# isg_adc_dac_test_board_top.net
KiCad netlist of a schematic drawn in Altium Designer
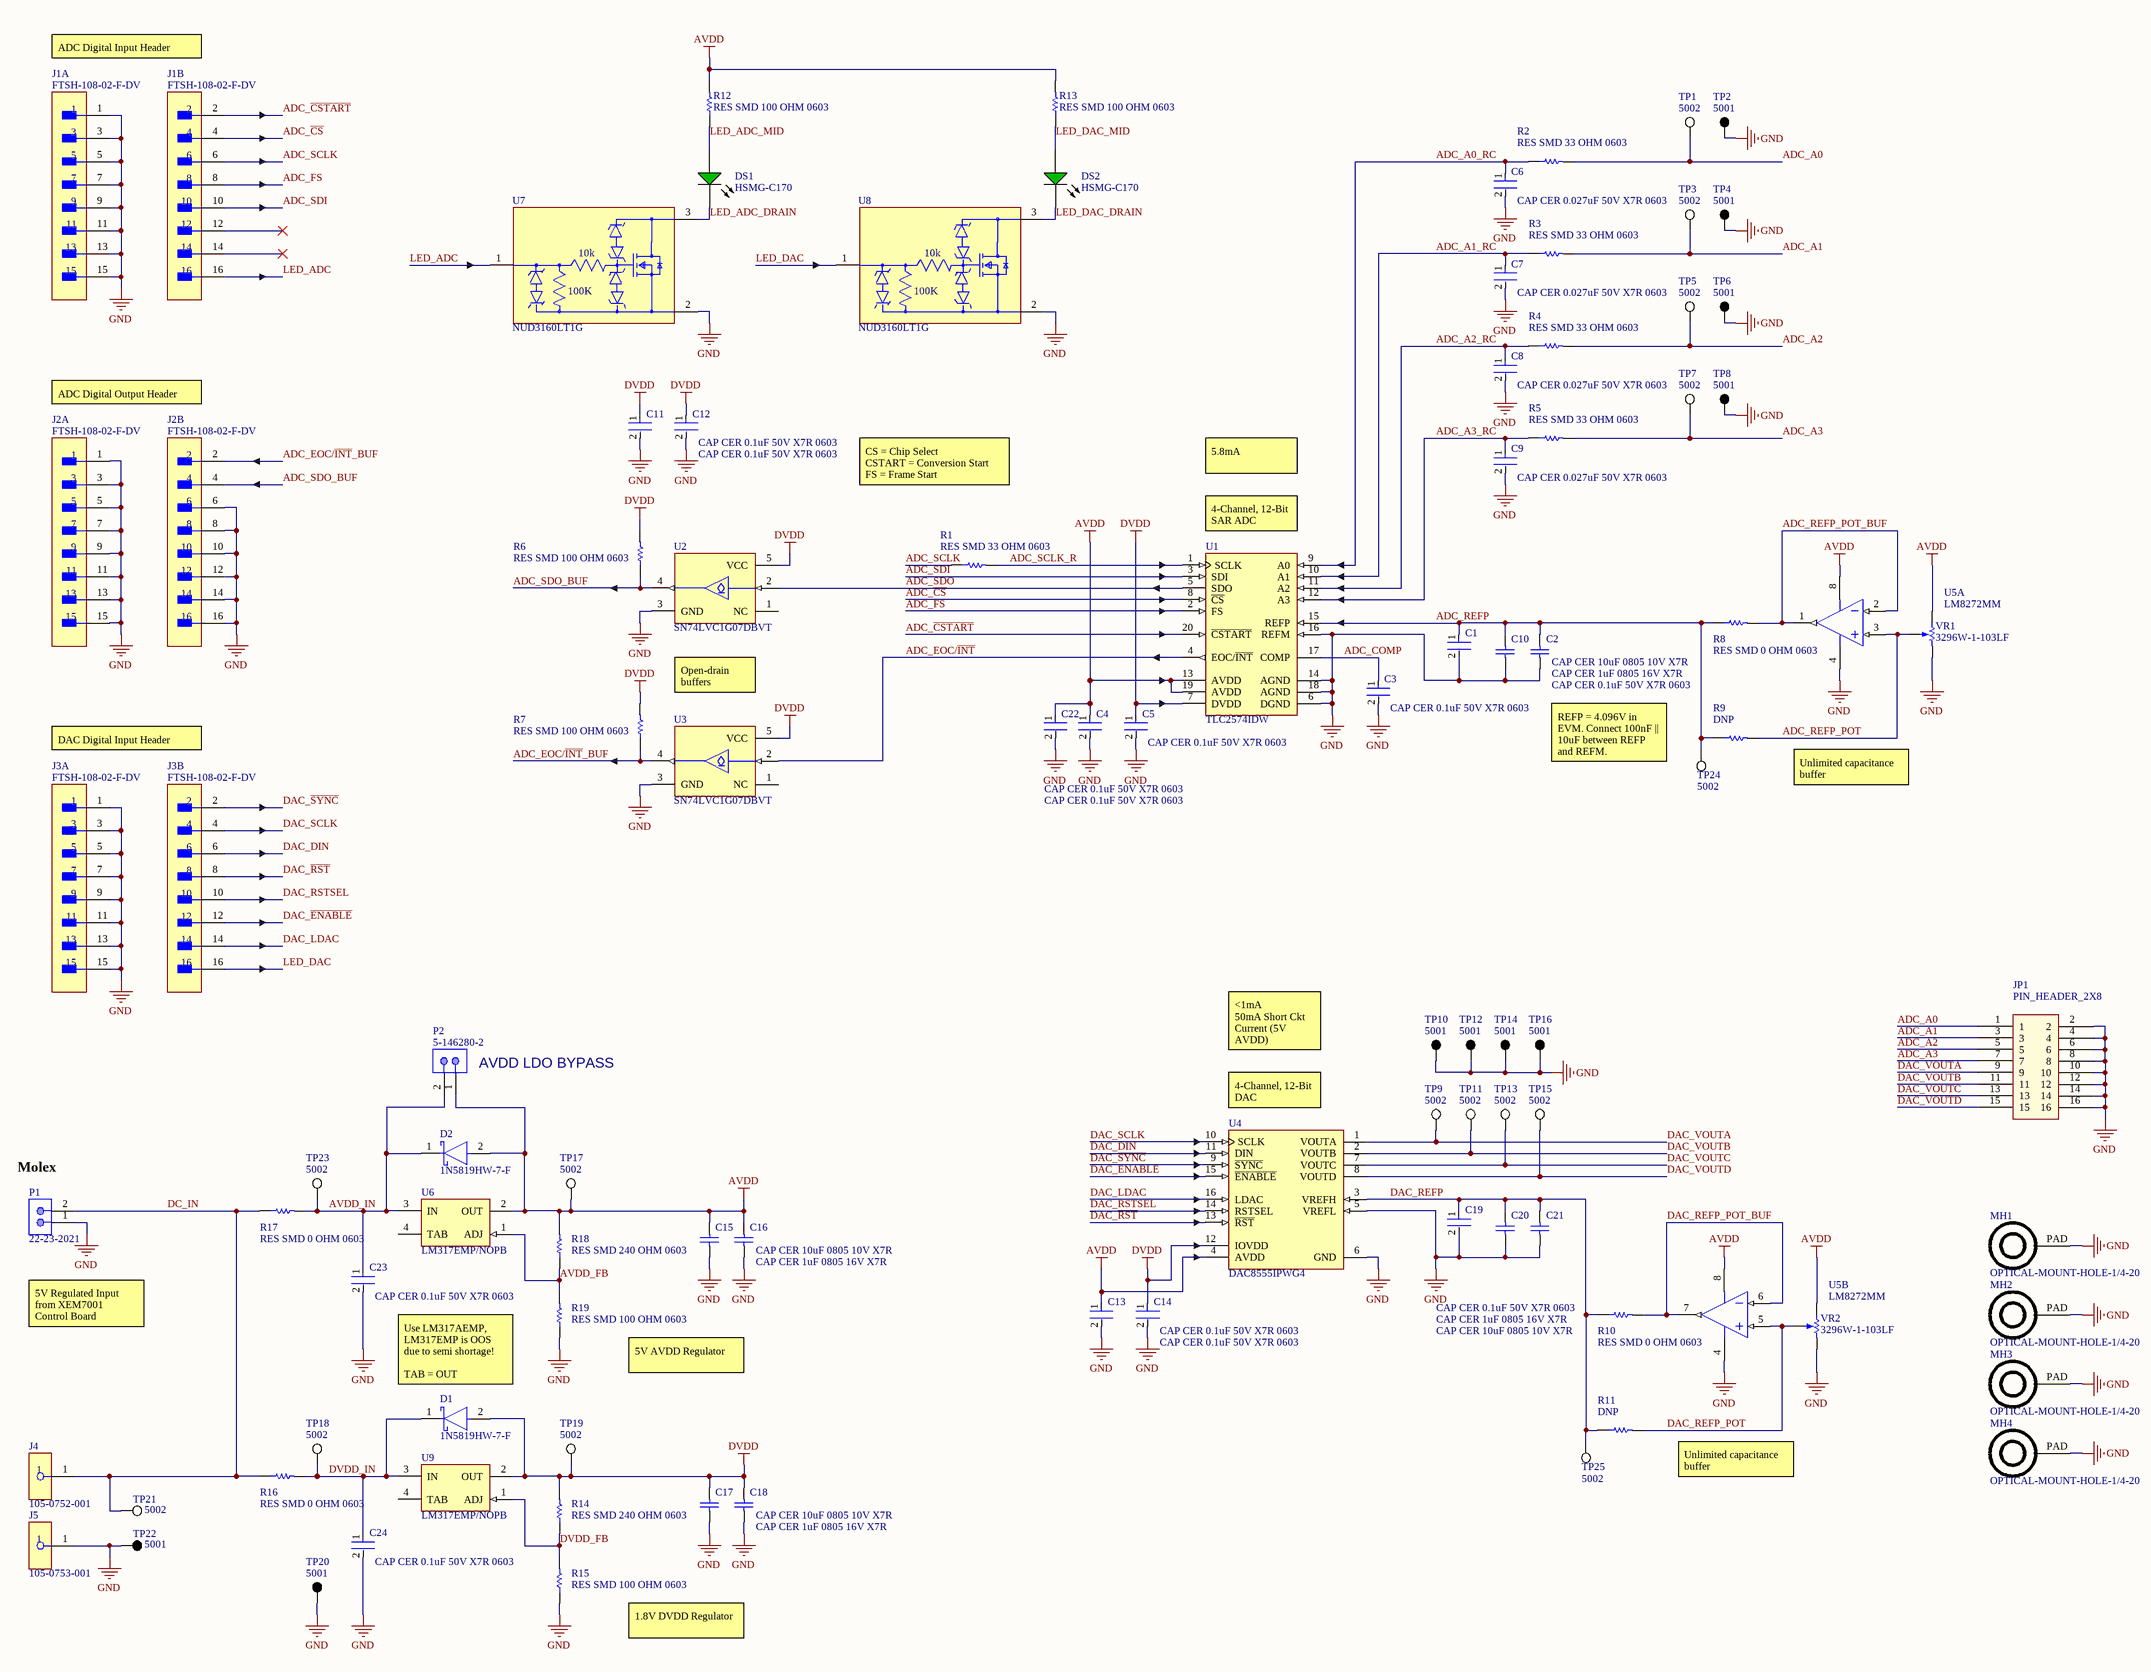
[diagram p0: isg_adc_dac_test_board_top.SchDoc]

(export (version "E")
  (design (tool "Eeschema 10.0.6"))
  (components
    (comp (ref "C1")
      (value "CAP CER 0.1uF 50V X7R 0603")
      (footprint "FP-CC0603-DA-MFG")
      (fields
        (field (name "OCTOPART") "https://octopart.com/cc0603krx7r7bb104-yageo-192941")
        (field (name "TOLERANCE") "0.1")
        (field (name "VOLTAGE") "16 V")
      )
      (libsource (lib "Altium Content Vault") (part "11868f565c42a9108669ba33697ecf6"))
    )
    (comp (ref "C2")
      (value "CAP CER 10uF 0805 10V X7R")
      (footprint "CAPC2013X140X50NL20T25")
      (fields
        (field (name "PART NUMBER") "0805ZC475KAT2A")
        (field (name "MANUFACTURER") "AVX Interconnect / Elco")
      )
      (libsource (lib "Altium Content Vault") (part "CAP"))
    )
    (comp (ref "C3")
      (value "CAP CER 0.1uF 50V X7R 0603")
      (footprint "FP-CC0603-DA-MFG")
      (fields
        (field (name "OCTOPART") "https://octopart.com/cc0603krx7r7bb104-yageo-192941")
        (field (name "TOLERANCE") "0.1")
        (field (name "VOLTAGE") "16 V")
      )
      (libsource (lib "Altium Content Vault") (part "11868f565c42a9108669ba33697ecf6"))
    )
    (comp (ref "C4")
      (value "CAP CER 0.1uF 50V X7R 0603")
      (footprint "FP-CC0603-DA-MFG")
      (fields
        (field (name "OCTOPART") "https://octopart.com/cc0603krx7r7bb104-yageo-192941")
        (field (name "TOLERANCE") "0.1")
        (field (name "VOLTAGE") "16 V")
      )
      (libsource (lib "Altium Content Vault") (part "11868f565c42a9108669ba33697ecf6"))
    )
    (comp (ref "C5")
      (value "CAP CER 0.1uF 50V X7R 0603")
      (footprint "FP-CC0603-DA-MFG")
      (fields
        (field (name "OCTOPART") "https://octopart.com/cc0603krx7r7bb104-yageo-192941")
        (field (name "TOLERANCE") "0.1")
        (field (name "VOLTAGE") "16 V")
      )
      (libsource (lib "Altium Content Vault") (part "11868f565c42a9108669ba33697ecf6"))
    )
    (comp (ref "C6")
      (value "CAP CER 0.027uF 50V X7R 0603")
      (footprint "FP-CC0603-DA-MFG")
      (fields
        (field (name "OCTOPART") "https://octopart.com/cc0603krx7r7bb104-yageo-192941")
        (field (name "TOLERANCE") "0.1")
        (field (name "VOLTAGE") "16 V")
      )
      (libsource (lib "Altium Content Vault") (part "11868f565c42a9108669ba33697ecf6"))
    )
    (comp (ref "C7")
      (value "CAP CER 0.027uF 50V X7R 0603")
      (footprint "FP-CC0603-DA-MFG")
      (fields
        (field (name "OCTOPART") "https://octopart.com/cc0603krx7r7bb104-yageo-192941")
        (field (name "TOLERANCE") "0.1")
        (field (name "VOLTAGE") "16 V")
      )
      (libsource (lib "Altium Content Vault") (part "11868f565c42a9108669ba33697ecf6"))
    )
    (comp (ref "C8")
      (value "CAP CER 0.027uF 50V X7R 0603")
      (footprint "FP-CC0603-DA-MFG")
      (fields
        (field (name "OCTOPART") "https://octopart.com/cc0603krx7r7bb104-yageo-192941")
        (field (name "TOLERANCE") "0.1")
        (field (name "VOLTAGE") "16 V")
      )
      (libsource (lib "Altium Content Vault") (part "11868f565c42a9108669ba33697ecf6"))
    )
    (comp (ref "C9")
      (value "CAP CER 0.027uF 50V X7R 0603")
      (footprint "FP-CC0603-DA-MFG")
      (fields
        (field (name "OCTOPART") "https://octopart.com/cc0603krx7r7bb104-yageo-192941")
        (field (name "TOLERANCE") "0.1")
        (field (name "VOLTAGE") "16 V")
      )
      (libsource (lib "Altium Content Vault") (part "11868f565c42a9108669ba33697ecf6"))
    )
    (comp (ref "C10")
      (value "CAP CER 1uF 0805 16V X7R")
      (footprint "CAPC2013X140X50NL20T25")
      (fields
        (field (name "PART NUMBER") "0805ZC475KAT2A")
        (field (name "MANUFACTURER") "AVX Interconnect / Elco")
      )
      (libsource (lib "Altium Content Vault") (part "CAP"))
    )
    (comp (ref "C11")
      (value "CAP CER 0.1uF 50V X7R 0603")
      (footprint "FP-CC0603-DA-MFG")
      (fields
        (field (name "OCTOPART") "https://octopart.com/cc0603krx7r7bb104-yageo-192941")
        (field (name "TOLERANCE") "0.1")
        (field (name "VOLTAGE") "16 V")
      )
      (libsource (lib "Altium Content Vault") (part "11868f565c42a9108669ba33697ecf6"))
    )
    (comp (ref "C12")
      (value "CAP CER 0.1uF 50V X7R 0603")
      (footprint "FP-CC0603-DA-MFG")
      (fields
        (field (name "OCTOPART") "https://octopart.com/cc0603krx7r7bb104-yageo-192941")
        (field (name "TOLERANCE") "0.1")
        (field (name "VOLTAGE") "16 V")
      )
      (libsource (lib "Altium Content Vault") (part "11868f565c42a9108669ba33697ecf6"))
    )
    (comp (ref "C13")
      (value "CAP CER 0.1uF 50V X7R 0603")
      (footprint "FP-CC0603-DA-MFG")
      (fields
        (field (name "OCTOPART") "https://octopart.com/cc0603krx7r7bb104-yageo-192941")
        (field (name "TOLERANCE") "0.1")
        (field (name "VOLTAGE") "16 V")
      )
      (libsource (lib "Altium Content Vault") (part "11868f565c42a9108669ba33697ecf6"))
    )
    (comp (ref "C14")
      (value "CAP CER 0.1uF 50V X7R 0603")
      (footprint "FP-CC0603-DA-MFG")
      (fields
        (field (name "OCTOPART") "https://octopart.com/cc0603krx7r7bb104-yageo-192941")
        (field (name "TOLERANCE") "0.1")
        (field (name "VOLTAGE") "16 V")
      )
      (libsource (lib "Altium Content Vault") (part "11868f565c42a9108669ba33697ecf6"))
    )
    (comp (ref "C15")
      (value "CAP CER 1uF 0805 16V X7R")
      (footprint "CAPC2013X140X50NL20T25")
      (fields
        (field (name "PART NUMBER") "0805ZC475KAT2A")
        (field (name "MANUFACTURER") "AVX Interconnect / Elco")
      )
      (libsource (lib "Altium Content Vault") (part "CAP"))
    )
    (comp (ref "C16")
      (value "CAP CER 10uF 0805 10V X7R")
      (footprint "CAPC2013X140X50NL20T25")
      (fields
        (field (name "PART NUMBER") "0805ZC475KAT2A")
        (field (name "MANUFACTURER") "AVX Interconnect / Elco")
      )
      (libsource (lib "Altium Content Vault") (part "CAP"))
    )
    (comp (ref "C17")
      (value "CAP CER 1uF 0805 16V X7R")
      (footprint "CAPC2013X140X50NL20T25")
      (fields
        (field (name "PART NUMBER") "0805ZC475KAT2A")
        (field (name "MANUFACTURER") "AVX Interconnect / Elco")
      )
      (libsource (lib "Altium Content Vault") (part "CAP"))
    )
    (comp (ref "C18")
      (value "CAP CER 10uF 0805 10V X7R")
      (footprint "CAPC2013X140X50NL20T25")
      (fields
        (field (name "PART NUMBER") "0805ZC475KAT2A")
        (field (name "MANUFACTURER") "AVX Interconnect / Elco")
      )
      (libsource (lib "Altium Content Vault") (part "CAP"))
    )
    (comp (ref "C19")
      (value "CAP CER 0.1uF 50V X7R 0603")
      (footprint "FP-CC0603-DA-MFG")
      (fields
        (field (name "OCTOPART") "https://octopart.com/cc0603krx7r7bb104-yageo-192941")
        (field (name "TOLERANCE") "0.1")
        (field (name "VOLTAGE") "16 V")
      )
      (libsource (lib "Altium Content Vault") (part "11868f565c42a9108669ba33697ecf6"))
    )
    (comp (ref "C20")
      (value "CAP CER 1uF 0805 16V X7R")
      (footprint "CAPC2013X140X50NL20T25")
      (fields
        (field (name "PART NUMBER") "0805ZC475KAT2A")
        (field (name "MANUFACTURER") "AVX Interconnect / Elco")
      )
      (libsource (lib "Altium Content Vault") (part "CAP"))
    )
    (comp (ref "C21")
      (value "CAP CER 10uF 0805 10V X7R")
      (footprint "CAPC2013X140X50NL20T25")
      (fields
        (field (name "PART NUMBER") "0805ZC475KAT2A")
        (field (name "MANUFACTURER") "AVX Interconnect / Elco")
      )
      (libsource (lib "Altium Content Vault") (part "CAP"))
    )
    (comp (ref "C22")
      (value "CAP CER 0.1uF 50V X7R 0603")
      (footprint "FP-CC0603-DA-MFG")
      (fields
        (field (name "OCTOPART") "https://octopart.com/cc0603krx7r7bb104-yageo-192941")
        (field (name "TOLERANCE") "0.1")
        (field (name "VOLTAGE") "16 V")
      )
      (libsource (lib "Altium Content Vault") (part "11868f565c42a9108669ba33697ecf6"))
    )
    (comp (ref "C23")
      (value "CAP CER 0.1uF 50V X7R 0603")
      (footprint "FP-CC0603-DA-MFG")
      (fields
        (field (name "OCTOPART") "https://octopart.com/cc0603krx7r7bb104-yageo-192941")
        (field (name "TOLERANCE") "0.1")
        (field (name "VOLTAGE") "16 V")
      )
      (libsource (lib "Altium Content Vault") (part "11868f565c42a9108669ba33697ecf6"))
    )
    (comp (ref "C24")
      (value "CAP CER 0.1uF 50V X7R 0603")
      (footprint "FP-CC0603-DA-MFG")
      (fields
        (field (name "OCTOPART") "https://octopart.com/cc0603krx7r7bb104-yageo-192941")
        (field (name "TOLERANCE") "0.1")
        (field (name "VOLTAGE") "16 V")
      )
      (libsource (lib "Altium Content Vault") (part "11868f565c42a9108669ba33697ecf6"))
    )
    (comp (ref "D1")
      (value "1N5819HW-7-F")
      (footprint "FP-SOD123-IPC_A")
      (description "DIODE SCHOTTKY 40V 1A SOD123")
      (libsource (lib "Altium Content Vault") (part "1d6ec82d83fb6aee721767c19dac4b9"))
    )
    (comp (ref "D2")
      (value "1N5819HW-7-F")
      (footprint "FP-SOD123-IPC_A")
      (description "DIODE SCHOTTKY 40V 1A SOD123")
      (libsource (lib "Altium Content Vault") (part "1d6ec82d83fb6aee721767c19dac4b9"))
    )
    (comp (ref "DS1")
      (value "HSMG-C170")
      (footprint "AVAG-HSMX-C170_V")
      (description "Chip LED, Green, 2.2 V, -40 to 85 degC, 2-Pin SMD, Pb-Free, Tape and Reel")
      (fields (field (name "MANUFACTURER") "Avago"))
      (libsource (lib "Altium Content Vault") (part "LED_GREEN_A1K2-2"))
    )
    (comp (ref "DS2")
      (value "HSMG-C170")
      (footprint "AVAG-HSMX-C170_V")
      (description "Chip LED, Green, 2.2 V, -40 to 85 degC, 2-Pin SMD, Pb-Free, Tape and Reel")
      (fields (field (name "MANUFACTURER") "Avago"))
      (libsource (lib "Altium Content Vault") (part "LED_GREEN_A1K2-2"))
    )
    (comp (ref "J1")
      (value "FTSH-108-02-F-DV")
      (footprint "FP-FTSH-108-02-F-DV-MFG")
      (description "CONN HEADER SMD 16POS 1.27MM")
      (fields
        (field (name "OCTOPART") "https://octopart.com/ftsh-108-02-f-dv-samtec-10605893")
        (field (name "MANUFACTURER") "Samtec")
      )
      (libsource (lib "Altium Content Vault") (part "4b6d22b45e2f925f038cba5d936fbcc"))
    )
    (comp (ref "J2")
      (value "FTSH-108-02-F-DV")
      (footprint "FP-FTSH-108-02-F-DV-MFG")
      (description "CONN HEADER SMD 16POS 1.27MM")
      (fields
        (field (name "OCTOPART") "https://octopart.com/ftsh-108-02-f-dv-samtec-10605893")
        (field (name "MANUFACTURER") "Samtec")
      )
      (libsource (lib "Altium Content Vault") (part "4b6d22b45e2f925f038cba5d936fbcc"))
    )
    (comp (ref "J3")
      (value "FTSH-108-02-F-DV")
      (footprint "FP-FTSH-108-02-F-DV-MFG")
      (description "CONN HEADER SMD 16POS 1.27MM")
      (fields
        (field (name "OCTOPART") "https://octopart.com/ftsh-108-02-f-dv-samtec-10605893")
        (field (name "MANUFACTURER") "Samtec")
      )
      (libsource (lib "Altium Content Vault") (part "4b6d22b45e2f925f038cba5d936fbcc"))
    )
    (comp (ref "J4")
      (value "105-0752-001")
      (footprint "FP-105-0751-001-MFG")
      (description "CONN TIP JACK SOLDER WHITE")
      (fields
        (field (name "MANUFACTURER") "Cinch Connectivity")
        (field (name "OCTOPART") "https://octopart.com/105-0751-001-cinch+connectivity+solutions-51372833")
      )
      (libsource (lib "Altium Content Vault") (part "98815daf2f2c152b0c43f5ab9800df6"))
    )
    (comp (ref "J5")
      (value "105-0753-001")
      (footprint "FP-105-0751-001-MFG")
      (description "CONN TIP JACK SOLDER WHITE")
      (fields
        (field (name "MANUFACTURER") "Cinch Connectivity")
        (field (name "OCTOPART") "https://octopart.com/105-0751-001-cinch+connectivity+solutions-51372833")
      )
      (libsource (lib "Altium Content Vault") (part "98815daf2f2c152b0c43f5ab9800df6"))
    )
    (comp (ref "JP1")
      (value "PIN_HEADER_2X8")
      (footprint "PIN_HEADER_2X8_2.54MM")
      (libsource (lib "headers") (part "PIN_HEADER_2X8"))
    )
    (comp (ref "MH1")
      (value "OPTICAL-MOUNT-HOLE-1/4-20")
      (footprint "mechanical:MH-1/4-20")
      (libsource (lib "mechanical") (part "OPTICAL-MOUNT-HOLE-1/4-20"))
    )
    (comp (ref "MH2")
      (value "OPTICAL-MOUNT-HOLE-1/4-20")
      (footprint "mechanical:MH-1/4-20")
      (libsource (lib "mechanical") (part "OPTICAL-MOUNT-HOLE-1/4-20"))
    )
    (comp (ref "MH3")
      (value "OPTICAL-MOUNT-HOLE-1/4-20")
      (footprint "mechanical:MH-1/4-20")
      (libsource (lib "mechanical") (part "OPTICAL-MOUNT-HOLE-1/4-20"))
    )
    (comp (ref "MH4")
      (value "OPTICAL-MOUNT-HOLE-1/4-20")
      (footprint "mechanical:MH-1/4-20")
      (libsource (lib "mechanical") (part "OPTICAL-MOUNT-HOLE-1/4-20"))
    )
    (comp (ref "P1")
      (value "22-23-2021")
      (footprint "MOLX-22-23-2021_V")
      (libsource (lib "Altium Content Vault") (part "CN-1P-M-R2"))
    )
    (comp (ref "P2")
      (value "5-146280-2")
      (footprint "TECO-5-146280-2_V")
      (fields (field (name "MANUFACTURER") "TE Connectivity"))
      (libsource (lib "") (part "CN-1P-M-R2_1"))
    )
    (comp (ref "R1")
      (value "RES SMD 33 OHM 0603")
      (footprint "RESC1609X50X30LL10T20")
      (fields (field (name "PART NUMBER") "CRCW0603100KFKEA") (field (name "MANUFACTURER") "Vishay Dale"))
      (libsource (lib "Altium Content Vault") (part "RES"))
    )
    (comp (ref "R2")
      (value "RES SMD 33 OHM 0603")
      (footprint "RESC1609X50X30LL10T20")
      (fields (field (name "PART NUMBER") "CRCW0603100KFKEA") (field (name "MANUFACTURER") "Vishay Dale"))
      (libsource (lib "Altium Content Vault") (part "RES"))
    )
    (comp (ref "R3")
      (value "RES SMD 33 OHM 0603")
      (footprint "RESC1609X50X30LL10T20")
      (fields (field (name "PART NUMBER") "CRCW0603100KFKEA") (field (name "MANUFACTURER") "Vishay Dale"))
      (libsource (lib "Altium Content Vault") (part "RES"))
    )
    (comp (ref "R4")
      (value "RES SMD 33 OHM 0603")
      (footprint "RESC1609X50X30LL10T20")
      (fields (field (name "PART NUMBER") "CRCW0603100KFKEA") (field (name "MANUFACTURER") "Vishay Dale"))
      (libsource (lib "Altium Content Vault") (part "RES"))
    )
    (comp (ref "R5")
      (value "RES SMD 33 OHM 0603")
      (footprint "RESC1609X50X30LL10T20")
      (fields (field (name "PART NUMBER") "CRCW0603100KFKEA") (field (name "MANUFACTURER") "Vishay Dale"))
      (libsource (lib "Altium Content Vault") (part "RES"))
    )
    (comp (ref "R6")
      (value "RES SMD 100 OHM 0603")
      (footprint "RESC1609X50X30LL10T20")
      (fields (field (name "PART NUMBER") "CRCW0603100KFKEA") (field (name "MANUFACTURER") "Vishay Dale"))
      (libsource (lib "Altium Content Vault") (part "RES"))
    )
    (comp (ref "R7")
      (value "RES SMD 100 OHM 0603")
      (footprint "RESC1609X50X30LL10T20")
      (fields (field (name "PART NUMBER") "CRCW0603100KFKEA") (field (name "MANUFACTURER") "Vishay Dale"))
      (libsource (lib "Altium Content Vault") (part "RES"))
    )
    (comp (ref "R8")
      (value "RES SMD 0 OHM 0603")
      (footprint "RESC1609X50X30LL10T20")
      (fields (field (name "PART NUMBER") "CRCW0603100KFKEA") (field (name "MANUFACTURER") "Vishay Dale"))
      (libsource (lib "Altium Content Vault") (part "RES"))
    )
    (comp (ref "R9")
      (value "DNP")
      (footprint "RESC1609X50X30LL10T20")
      (fields (field (name "PART NUMBER") "CRCW0603100KFKEA") (field (name "MANUFACTURER") "Vishay Dale"))
      (libsource (lib "Altium Content Vault") (part "RES"))
    )
    (comp (ref "R10")
      (value "RES SMD 0 OHM 0603")
      (footprint "RESC1609X50X30LL10T20")
      (fields (field (name "PART NUMBER") "CRCW0603100KFKEA") (field (name "MANUFACTURER") "Vishay Dale"))
      (libsource (lib "Altium Content Vault") (part "RES"))
    )
    (comp (ref "R11")
      (value "DNP")
      (footprint "RESC1609X50X30LL10T20")
      (fields (field (name "PART NUMBER") "CRCW0603100KFKEA") (field (name "MANUFACTURER") "Vishay Dale"))
      (libsource (lib "Altium Content Vault") (part "RES"))
    )
    (comp (ref "R12")
      (value "RES SMD 100 OHM 0603")
      (footprint "RESC1609X50X30LL10T20")
      (fields (field (name "PART NUMBER") "CRCW0603100KFKEA") (field (name "MANUFACTURER") "Vishay Dale"))
      (libsource (lib "Altium Content Vault") (part "RES"))
    )
    (comp (ref "R13")
      (value "RES SMD 100 OHM 0603")
      (footprint "RESC1609X50X30LL10T20")
      (fields (field (name "PART NUMBER") "CRCW0603100KFKEA") (field (name "MANUFACTURER") "Vishay Dale"))
      (libsource (lib "Altium Content Vault") (part "RES"))
    )
    (comp (ref "R14")
      (value "RES SMD 240 OHM 0603")
      (footprint "RESC1609X50X30LL10T20")
      (fields (field (name "PART NUMBER") "CRCW0603100KFKEA") (field (name "MANUFACTURER") "Vishay Dale"))
      (libsource (lib "Altium Content Vault") (part "RES"))
    )
    (comp (ref "R15")
      (value "RES SMD 100 OHM 0603")
      (footprint "RESC1609X50X30LL10T20")
      (fields (field (name "PART NUMBER") "CRCW0603100KFKEA") (field (name "MANUFACTURER") "Vishay Dale"))
      (libsource (lib "Altium Content Vault") (part "RES"))
    )
    (comp (ref "R16")
      (value "RES SMD 0 OHM 0603")
      (footprint "RESC1609X50X30LL10T20")
      (fields (field (name "PART NUMBER") "CRCW0603100KFKEA") (field (name "MANUFACTURER") "Vishay Dale"))
      (libsource (lib "Altium Content Vault") (part "RES"))
    )
    (comp (ref "R17")
      (value "RES SMD 0 OHM 0603")
      (footprint "RESC1609X50X30LL10T20")
      (fields (field (name "PART NUMBER") "CRCW0603100KFKEA") (field (name "MANUFACTURER") "Vishay Dale"))
      (libsource (lib "Altium Content Vault") (part "RES"))
    )
    (comp (ref "R18")
      (value "RES SMD 240 OHM 0603")
      (footprint "RESC1609X50X30LL10T20")
      (fields (field (name "PART NUMBER") "CRCW0603100KFKEA") (field (name "MANUFACTURER") "Vishay Dale"))
      (libsource (lib "Altium Content Vault") (part "RES"))
    )
    (comp (ref "R19")
      (value "RES SMD 100 OHM 0603")
      (footprint "RESC1609X50X30LL10T20")
      (fields (field (name "PART NUMBER") "CRCW0603100KFKEA") (field (name "MANUFACTURER") "Vishay Dale"))
      (libsource (lib "Altium Content Vault") (part "RES"))
    )
    (comp (ref "TP1")
      (value "5002")
      (footprint "KSTN-5002")
      (description "Test Point, White, 1-Pin THD, RoHS, Bulk")
      (fields (field (name "MANUFACTURER") "KeystoneElectronics"))
      (libsource (lib "Altium Content Vault") (part "KSTN-TP-5002"))
    )
    (comp (ref "TP2")
      (value "5001")
      (footprint "KSTN-5001")
      (description "Test Point, Black, 1-Pin THD, RoHS, Bulk")
      (fields (field (name "MANUFACTURER") "Keystone"))
      (libsource (lib "Altium Content Vault") (part "KSTN-TP-5001"))
    )
    (comp (ref "TP3")
      (value "5002")
      (footprint "KSTN-5002")
      (description "Test Point, White, 1-Pin THD, RoHS, Bulk")
      (fields (field (name "MANUFACTURER") "KeystoneElectronics"))
      (libsource (lib "Altium Content Vault") (part "KSTN-TP-5002"))
    )
    (comp (ref "TP4")
      (value "5001")
      (footprint "KSTN-5001")
      (description "Test Point, Black, 1-Pin THD, RoHS, Bulk")
      (fields (field (name "MANUFACTURER") "Keystone"))
      (libsource (lib "Altium Content Vault") (part "KSTN-TP-5001"))
    )
    (comp (ref "TP5")
      (value "5002")
      (footprint "KSTN-5002")
      (description "Test Point, White, 1-Pin THD, RoHS, Bulk")
      (fields (field (name "MANUFACTURER") "KeystoneElectronics"))
      (libsource (lib "Altium Content Vault") (part "KSTN-TP-5002"))
    )
    (comp (ref "TP6")
      (value "5001")
      (footprint "KSTN-5001")
      (description "Test Point, Black, 1-Pin THD, RoHS, Bulk")
      (fields (field (name "MANUFACTURER") "Keystone"))
      (libsource (lib "Altium Content Vault") (part "KSTN-TP-5001"))
    )
    (comp (ref "TP7")
      (value "5002")
      (footprint "KSTN-5002")
      (description "Test Point, White, 1-Pin THD, RoHS, Bulk")
      (fields (field (name "MANUFACTURER") "KeystoneElectronics"))
      (libsource (lib "Altium Content Vault") (part "KSTN-TP-5002"))
    )
    (comp (ref "TP8")
      (value "5001")
      (footprint "KSTN-5001")
      (description "Test Point, Black, 1-Pin THD, RoHS, Bulk")
      (fields (field (name "MANUFACTURER") "Keystone"))
      (libsource (lib "Altium Content Vault") (part "KSTN-TP-5001"))
    )
    (comp (ref "TP9")
      (value "5002")
      (footprint "KSTN-5002")
      (description "Test Point, White, 1-Pin THD, RoHS, Bulk")
      (fields (field (name "MANUFACTURER") "KeystoneElectronics"))
      (libsource (lib "Altium Content Vault") (part "KSTN-TP-5002"))
    )
    (comp (ref "TP10")
      (value "5001")
      (footprint "KSTN-5001")
      (description "Test Point, Black, 1-Pin THD, RoHS, Bulk")
      (fields (field (name "MANUFACTURER") "Keystone"))
      (libsource (lib "Altium Content Vault") (part "KSTN-TP-5001"))
    )
    (comp (ref "TP11")
      (value "5002")
      (footprint "KSTN-5002")
      (description "Test Point, White, 1-Pin THD, RoHS, Bulk")
      (fields (field (name "MANUFACTURER") "KeystoneElectronics"))
      (libsource (lib "Altium Content Vault") (part "KSTN-TP-5002"))
    )
    (comp (ref "TP12")
      (value "5001")
      (footprint "KSTN-5001")
      (description "Test Point, Black, 1-Pin THD, RoHS, Bulk")
      (fields (field (name "MANUFACTURER") "Keystone"))
      (libsource (lib "Altium Content Vault") (part "KSTN-TP-5001"))
    )
    (comp (ref "TP13")
      (value "5002")
      (footprint "KSTN-5002")
      (description "Test Point, White, 1-Pin THD, RoHS, Bulk")
      (fields (field (name "MANUFACTURER") "KeystoneElectronics"))
      (libsource (lib "Altium Content Vault") (part "KSTN-TP-5002"))
    )
    (comp (ref "TP14")
      (value "5001")
      (footprint "KSTN-5001")
      (description "Test Point, Black, 1-Pin THD, RoHS, Bulk")
      (fields (field (name "MANUFACTURER") "Keystone"))
      (libsource (lib "Altium Content Vault") (part "KSTN-TP-5001"))
    )
    (comp (ref "TP15")
      (value "5002")
      (footprint "KSTN-5002")
      (description "Test Point, White, 1-Pin THD, RoHS, Bulk")
      (fields (field (name "MANUFACTURER") "KeystoneElectronics"))
      (libsource (lib "Altium Content Vault") (part "KSTN-TP-5002"))
    )
    (comp (ref "TP16")
      (value "5001")
      (footprint "KSTN-5001")
      (description "Test Point, Black, 1-Pin THD, RoHS, Bulk")
      (fields (field (name "MANUFACTURER") "Keystone"))
      (libsource (lib "Altium Content Vault") (part "KSTN-TP-5001"))
    )
    (comp (ref "TP17")
      (value "5002")
      (footprint "KSTN-5002")
      (description "Test Point, White, 1-Pin THD, RoHS, Bulk")
      (fields (field (name "MANUFACTURER") "KeystoneElectronics"))
      (libsource (lib "Altium Content Vault") (part "KSTN-TP-5002"))
    )
    (comp (ref "TP18")
      (value "5002")
      (footprint "KSTN-5002")
      (description "Test Point, White, 1-Pin THD, RoHS, Bulk")
      (fields (field (name "MANUFACTURER") "KeystoneElectronics"))
      (libsource (lib "Altium Content Vault") (part "KSTN-TP-5002"))
    )
    (comp (ref "TP19")
      (value "5002")
      (footprint "KSTN-5002")
      (description "Test Point, White, 1-Pin THD, RoHS, Bulk")
      (fields (field (name "MANUFACTURER") "KeystoneElectronics"))
      (libsource (lib "Altium Content Vault") (part "KSTN-TP-5002"))
    )
    (comp (ref "TP20")
      (value "5001")
      (footprint "KSTN-5001")
      (description "Test Point, Black, 1-Pin THD, RoHS, Bulk")
      (fields (field (name "MANUFACTURER") "Keystone"))
      (libsource (lib "Altium Content Vault") (part "KSTN-TP-5001"))
    )
    (comp (ref "TP21")
      (value "5002")
      (footprint "KSTN-5002")
      (description "Test Point, White, 1-Pin THD, RoHS, Bulk")
      (fields (field (name "MANUFACTURER") "KeystoneElectronics"))
      (libsource (lib "Altium Content Vault") (part "KSTN-TP-5002"))
    )
    (comp (ref "TP22")
      (value "5001")
      (footprint "KSTN-5001")
      (description "Test Point, Black, 1-Pin THD, RoHS, Bulk")
      (fields (field (name "MANUFACTURER") "Keystone"))
      (libsource (lib "Altium Content Vault") (part "KSTN-TP-5001"))
    )
    (comp (ref "TP23")
      (value "5002")
      (footprint "KSTN-5002")
      (description "Test Point, White, 1-Pin THD, RoHS, Bulk")
      (fields (field (name "MANUFACTURER") "KeystoneElectronics"))
      (libsource (lib "Altium Content Vault") (part "KSTN-TP-5002"))
    )
    (comp (ref "TP24")
      (value "5002")
      (footprint "KSTN-5002")
      (description "Test Point, White, 1-Pin THD, RoHS, Bulk")
      (fields (field (name "MANUFACTURER") "KeystoneElectronics"))
      (libsource (lib "Altium Content Vault") (part "KSTN-TP-5002"))
    )
    (comp (ref "TP25")
      (value "5002")
      (footprint "KSTN-5002")
      (description "Test Point, White, 1-Pin THD, RoHS, Bulk")
      (fields (field (name "MANUFACTURER") "KeystoneElectronics"))
      (libsource (lib "Altium Content Vault") (part "KSTN-TP-5002"))
    )
    (comp (ref "U1")
      (value "TLC2574IDW")
      (footprint "TI-DW20_L")
      (fields (field (name "MANUFACTURER") "Texas Instruments"))
      (libsource (lib "Altium Content Vault") (part "TI-TLC2574DW20"))
    )
    (comp (ref "U2")
      (value "SN74LVC1G07DBVT")
      (footprint "FP-DBV0005A-MFG")
      (description "IC BUF NON-INVERT 5.5V SOT23-5")
      (fields
        (field (name "MANUFACTURER") "Texas Instruments")
        (field (name "OCTOPART") "https://octopart.com/sn74lvc1g07dbvt-texas+instruments-1006798")
      )
      (libsource (lib "Altium Content Vault") (part "c70ff603b92c9fc986899d9593dc2c3"))
    )
    (comp (ref "U3")
      (value "SN74LVC1G07DBVT")
      (footprint "FP-DBV0005A-MFG")
      (description "IC BUF NON-INVERT 5.5V SOT23-5")
      (fields
        (field (name "MANUFACTURER") "Texas Instruments")
        (field (name "OCTOPART") "https://octopart.com/sn74lvc1g07dbvt-texas+instruments-1006798")
      )
      (libsource (lib "Altium Content Vault") (part "c70ff603b92c9fc986899d9593dc2c3"))
    )
    (comp (ref "U4")
      (value "DAC8555IPWG4")
      (footprint "TI-PW16_L")
      (fields (field (name "MANUFACTURER") "Texas Instruments"))
      (libsource (lib "Altium Content Vault") (part "TI-DAC8555PW16"))
    )
    (comp (ref "U5")
      (value "LM8272MM")
      (footprint "DGK0008A_L")
      (description "RRIO, High Output Current & Unlimited Cap Load Op Amp, 8-pin Mini SOIC")
      (fields (field (name "MANUFACTURER") "Texas Instruments"))
      (libsource (lib "Altium Content Vault") (part "AMP-OPA-LM6132-8"))
    )
    (comp (ref "U6")
      (value "LM317EMP/NOPB")
      (footprint "DCY0004A_L")
      (description "3-Terminal Adjustable Regulator, 4-pin SOT-223, Pb-Free")
      (fields (field (name "MANUFACTURER") "Texas Instruments"))
      (libsource (lib "Altium Content Vault") (part "PM-REG-LM317ADJ-SOT4"))
    )
    (comp (ref "U7")
      (value "NUD3160LT1G")
      (footprint "FP-318-08-MFG")
      (description "IC INDCT LOAD DRVR INDUST SOT23")
      (fields
        (field (name "OCTOPART") "https://octopart.com/nud3160lt1g-on+semiconductor-470723")
        (field (name "MANUFACTURER") "ON Semiconductor")
      )
      (libsource (lib "Altium Content Vault") (part "3565ae214b0a124fee97343a38643ca"))
    )
    (comp (ref "U8")
      (value "NUD3160LT1G")
      (footprint "FP-318-08-MFG")
      (description "IC INDCT LOAD DRVR INDUST SOT23")
      (fields
        (field (name "OCTOPART") "https://octopart.com/nud3160lt1g-on+semiconductor-470723")
        (field (name "MANUFACTURER") "ON Semiconductor")
      )
      (libsource (lib "Altium Content Vault") (part "3565ae214b0a124fee97343a38643ca"))
    )
    (comp (ref "U9")
      (value "LM317EMP/NOPB")
      (footprint "DCY0004A_L")
      (description "3-Terminal Adjustable Regulator, 4-pin SOT-223, Pb-Free")
      (fields (field (name "MANUFACTURER") "Texas Instruments"))
      (libsource (lib "Altium Content Vault") (part "PM-REG-LM317ADJ-SOT4"))
    )
    (comp (ref "VR1")
      (value "3296W-1-103LF")
      (footprint "BOUR-3296W")
      (fields (field (name "TOLERANCE") "1%"))
      (libsource (lib "Altium Content Vault") (part "RES-POT-3"))
    )
    (comp (ref "VR2")
      (value "3296W-1-103LF")
      (footprint "BOUR-3296W")
      (fields (field (name "TOLERANCE") "1%"))
      (libsource (lib "Altium Content Vault") (part "RES-POT-3"))
    )
  )
  (nets
    (net (code "1") (name "/ADC_A0") (class "Default")
      (node (ref "JP1") (pin "1") (pinfunction "1_1") (pintype "passive"))
      (node (ref "R2") (pin "2") (pinfunction "2_2") (pintype "passive"))
      (node (ref "TP1") (pin "1") (pintype "passive"))
    )
    (net (code "2") (name "/ADC_A0_RC") (class "Default")
      (node (ref "C6") (pin "1") (pinfunction "1_1") (pintype "passive"))
      (node (ref "R2") (pin "1") (pinfunction "1_1") (pintype "passive"))
      (node (ref "U1") (pin "9") (pinfunction "A0_9") (pintype "input"))
    )
    (net (code "3") (name "/ADC_A1") (class "Default")
      (node (ref "JP1") (pin "3") (pinfunction "3_3") (pintype "passive"))
      (node (ref "R3") (pin "2") (pinfunction "2_2") (pintype "passive"))
      (node (ref "TP3") (pin "1") (pintype "passive"))
    )
    (net (code "4") (name "/ADC_A1_RC") (class "Default")
      (node (ref "C7") (pin "1") (pinfunction "1_1") (pintype "passive"))
      (node (ref "R3") (pin "1") (pinfunction "1_1") (pintype "passive"))
      (node (ref "U1") (pin "10") (pinfunction "A1_10") (pintype "input"))
    )
    (net (code "5") (name "/ADC_A2") (class "Default")
      (node (ref "JP1") (pin "5") (pinfunction "5_5") (pintype "passive"))
      (node (ref "R4") (pin "2") (pinfunction "2_2") (pintype "passive"))
      (node (ref "TP5") (pin "1") (pintype "passive"))
    )
    (net (code "6") (name "/ADC_A2_RC") (class "Default")
      (node (ref "C8") (pin "1") (pinfunction "1_1") (pintype "passive"))
      (node (ref "R4") (pin "1") (pinfunction "1_1") (pintype "passive"))
      (node (ref "U1") (pin "11") (pinfunction "A2_11") (pintype "input"))
    )
    (net (code "7") (name "/ADC_A3") (class "Default")
      (node (ref "JP1") (pin "7") (pinfunction "7_7") (pintype "passive"))
      (node (ref "R5") (pin "2") (pinfunction "2_2") (pintype "passive"))
      (node (ref "TP7") (pin "1") (pintype "passive"))
    )
    (net (code "8") (name "/ADC_A3_RC") (class "Default")
      (node (ref "C9") (pin "1") (pinfunction "1_1") (pintype "passive"))
      (node (ref "R5") (pin "1") (pinfunction "1_1") (pintype "passive"))
      (node (ref "U1") (pin "12") (pinfunction "A3_12") (pintype "input"))
    )
    (net (code "9") (name "/ADC_COMP") (class "Default")
      (node (ref "C3") (pin "1") (pinfunction "1_1") (pintype "passive"))
      (node (ref "U1") (pin "17") (pinfunction "COMP_17") (pintype "passive"))
    )
    (net (code "10") (name "/ADC_EOC{slash}~{INT}") (class "Default")
      (node (ref "U1") (pin "4") (pinfunction "EOC/~{INT}_4") (pintype "output"))
      (node (ref "U3") (pin "2") (pinfunction "A_2") (pintype "input"))
    )
    (net (code "11") (name "/ADC_EOC{slash}~{INT}_BUF") (class "Default")
      (node (ref "J2") (pin "2") (pinfunction "2_2") (pintype "passive"))
      (node (ref "R7") (pin "1") (pinfunction "1_1") (pintype "passive"))
      (node (ref "U3") (pin "4") (pinfunction "Y_4") (pintype "output"))
    )
    (net (code "12") (name "/ADC_FS") (class "Default")
      (node (ref "J1") (pin "8") (pinfunction "8_8") (pintype "passive"))
      (node (ref "U1") (pin "2") (pinfunction "FS_2") (pintype "input"))
    )
    (net (code "13") (name "/ADC_REFP") (class "Default")
      (node (ref "C1") (pin "1") (pinfunction "1_1") (pintype "passive"))
      (node (ref "C10") (pin "1") (pinfunction "1_1") (pintype "passive"))
      (node (ref "C2") (pin "1") (pinfunction "1_1") (pintype "passive"))
      (node (ref "R8") (pin "1") (pinfunction "1_1") (pintype "passive"))
      (node (ref "R9") (pin "1") (pinfunction "1_1") (pintype "passive"))
      (node (ref "TP24") (pin "1") (pintype "passive"))
      (node (ref "U1") (pin "15") (pinfunction "REFP_15") (pintype "input"))
    )
    (net (code "14") (name "/ADC_REFP_POT") (class "Default")
      (node (ref "R9") (pin "2") (pinfunction "2_2") (pintype "passive"))
      (node (ref "U5") (pin "3") (pinfunction "INA+_3") (pintype "input"))
      (node (ref "VR1") (pin "2") (pinfunction "S_2") (pintype "passive"))
    )
    (net (code "15") (name "/ADC_REFP_POT_BUF") (class "Default")
      (node (ref "R8") (pin "2") (pinfunction "2_2") (pintype "passive"))
      (node (ref "U5") (pin "1") (pinfunction "OUTA_1") (pintype "output"))
      (node (ref "U5") (pin "2") (pinfunction "INA-_2") (pintype "input"))
    )
    (net (code "16") (name "/ADC_SCLK") (class "Default")
      (node (ref "J1") (pin "6") (pinfunction "6_6") (pintype "passive"))
      (node (ref "R1") (pin "1") (pinfunction "1_1") (pintype "passive"))
    )
    (net (code "17") (name "/ADC_SCLK_R") (class "Default")
      (node (ref "R1") (pin "2") (pinfunction "2_2") (pintype "passive"))
      (node (ref "U1") (pin "1") (pinfunction "SCLK_1") (pintype "input"))
    )
    (net (code "18") (name "/ADC_SDI") (class "Default")
      (node (ref "J1") (pin "10") (pinfunction "10_10") (pintype "passive"))
      (node (ref "U1") (pin "3") (pinfunction "SDI_3") (pintype "input"))
    )
    (net (code "19") (name "/ADC_SDO") (class "Default")
      (node (ref "U1") (pin "5") (pinfunction "SDO_5") (pintype "tri_state"))
      (node (ref "U2") (pin "2") (pinfunction "A_2") (pintype "input"))
    )
    (net (code "20") (name "/ADC_SDO_BUF") (class "Default")
      (node (ref "J2") (pin "4") (pinfunction "4_4") (pintype "passive"))
      (node (ref "R6") (pin "1") (pinfunction "1_1") (pintype "passive"))
      (node (ref "U2") (pin "4") (pinfunction "Y_4") (pintype "output"))
    )
    (net (code "21") (name "/ADC_~{CSTART}") (class "Default")
      (node (ref "J1") (pin "2") (pinfunction "2_2") (pintype "passive"))
      (node (ref "U1") (pin "20") (pinfunction "~{CSTART}_20") (pintype "input"))
    )
    (net (code "22") (name "/ADC_~{CS}") (class "Default")
      (node (ref "J1") (pin "4") (pinfunction "4_4") (pintype "passive"))
      (node (ref "U1") (pin "8") (pinfunction "~{CS}_8") (pintype "input"))
    )
    (net (code "23") (name "/AVDD_FB") (class "Default")
      (node (ref "R18") (pin "1") (pinfunction "1_1") (pintype "passive"))
      (node (ref "R19") (pin "2") (pinfunction "2_2") (pintype "passive"))
      (node (ref "U6") (pin "1") (pinfunction "ADJ_1") (pintype "input"))
    )
    (net (code "24") (name "/AVDD_IN") (class "Default")
      (node (ref "C23") (pin "1") (pinfunction "1_1") (pintype "passive"))
      (node (ref "D2") (pin "1") (pinfunction "C_1") (pintype "passive"))
      (node (ref "P2") (pin "2") (pinfunction "2_2") (pintype "passive"))
      (node (ref "R17") (pin "2") (pinfunction "2_2") (pintype "passive"))
      (node (ref "TP23") (pin "1") (pintype "passive"))
      (node (ref "U6") (pin "3") (pinfunction "IN_3") (pintype "power_in"))
    )
    (net (code "25") (name "/DAC_DIN") (class "Default")
      (node (ref "J3") (pin "6") (pinfunction "6_6") (pintype "passive"))
      (node (ref "U4") (pin "11") (pinfunction "DIN_11") (pintype "input"))
    )
    (net (code "26") (name "/DAC_LDAC") (class "Default")
      (node (ref "J3") (pin "14") (pinfunction "14_14") (pintype "passive"))
      (node (ref "U4") (pin "16") (pinfunction "LDAC_16") (pintype "input"))
    )
    (net (code "27") (name "/DAC_REFP") (class "Default")
      (node (ref "C19") (pin "1") (pinfunction "1_1") (pintype "passive"))
      (node (ref "C20") (pin "1") (pinfunction "1_1") (pintype "passive"))
      (node (ref "C21") (pin "1") (pinfunction "1_1") (pintype "passive"))
      (node (ref "R10") (pin "1") (pinfunction "1_1") (pintype "passive"))
      (node (ref "R11") (pin "1") (pinfunction "1_1") (pintype "passive"))
      (node (ref "TP25") (pin "1") (pintype "passive"))
      (node (ref "U4") (pin "3") (pinfunction "VREFH_3") (pintype "input"))
    )
    (net (code "28") (name "/DAC_REFP_POT") (class "Default")
      (node (ref "R11") (pin "2") (pinfunction "2_2") (pintype "passive"))
      (node (ref "U5") (pin "5") (pinfunction "INB+_5") (pintype "input"))
      (node (ref "VR2") (pin "2") (pinfunction "S_2") (pintype "passive"))
    )
    (net (code "29") (name "/DAC_REFP_POT_BUF") (class "Default")
      (node (ref "R10") (pin "2") (pinfunction "2_2") (pintype "passive"))
      (node (ref "U5") (pin "6") (pinfunction "INB-_6") (pintype "input"))
      (node (ref "U5") (pin "7") (pinfunction "OUTB_7") (pintype "output"))
    )
    (net (code "30") (name "/DAC_RSTSEL") (class "Default")
      (node (ref "J3") (pin "10") (pinfunction "10_10") (pintype "passive"))
      (node (ref "U4") (pin "14") (pinfunction "RSTSEL_14") (pintype "input"))
    )
    (net (code "31") (name "/DAC_SCLK") (class "Default")
      (node (ref "J3") (pin "4") (pinfunction "4_4") (pintype "passive"))
      (node (ref "U4") (pin "10") (pinfunction "SCLK_10") (pintype "input"))
    )
    (net (code "32") (name "/DAC_VOUTA") (class "Default")
      (node (ref "JP1") (pin "9") (pinfunction "9_9") (pintype "passive"))
      (node (ref "TP9") (pin "1") (pintype "passive"))
      (node (ref "U4") (pin "1") (pinfunction "VOUTA_1") (pintype "tri_state"))
    )
    (net (code "33") (name "/DAC_VOUTB") (class "Default")
      (node (ref "JP1") (pin "11") (pinfunction "11_11") (pintype "passive"))
      (node (ref "TP11") (pin "1") (pintype "passive"))
      (node (ref "U4") (pin "2") (pinfunction "VOUTB_2") (pintype "tri_state"))
    )
    (net (code "34") (name "/DAC_VOUTC") (class "Default")
      (node (ref "JP1") (pin "13") (pinfunction "13_13") (pintype "passive"))
      (node (ref "TP13") (pin "1") (pintype "passive"))
      (node (ref "U4") (pin "7") (pinfunction "VOUTC_7") (pintype "tri_state"))
    )
    (net (code "35") (name "/DAC_VOUTD") (class "Default")
      (node (ref "JP1") (pin "15") (pinfunction "15_15") (pintype "passive"))
      (node (ref "TP15") (pin "1") (pintype "passive"))
      (node (ref "U4") (pin "8") (pinfunction "VOUTD_8") (pintype "tri_state"))
    )
    (net (code "36") (name "/DAC_~{ENABLE}") (class "Default")
      (node (ref "J3") (pin "12") (pinfunction "12_12") (pintype "passive"))
      (node (ref "U4") (pin "15") (pinfunction "~{ENABLE}_15") (pintype "input"))
    )
    (net (code "37") (name "/DAC_~{RST}") (class "Default")
      (node (ref "J3") (pin "8") (pinfunction "8_8") (pintype "passive"))
      (node (ref "U4") (pin "13") (pinfunction "~{RST}_13") (pintype "input"))
    )
    (net (code "38") (name "/DAC_~{SYNC}") (class "Default")
      (node (ref "J3") (pin "2") (pinfunction "2_2") (pintype "passive"))
      (node (ref "U4") (pin "9") (pinfunction "~{SYNC}_9") (pintype "input"))
    )
    (net (code "39") (name "/DC_IN") (class "Default")
      (node (ref "J4") (pin "1") (pinfunction "1_1") (pintype "passive"))
      (node (ref "P1") (pin "2") (pinfunction "2_2") (pintype "passive"))
      (node (ref "R16") (pin "1") (pinfunction "1_1") (pintype "passive"))
      (node (ref "R17") (pin "1") (pinfunction "1_1") (pintype "passive"))
      (node (ref "TP21") (pin "1") (pintype "passive"))
    )
    (net (code "40") (name "/DVDD_FB") (class "Default")
      (node (ref "R14") (pin "1") (pinfunction "1_1") (pintype "passive"))
      (node (ref "R15") (pin "2") (pinfunction "2_2") (pintype "passive"))
      (node (ref "U9") (pin "1") (pinfunction "ADJ_1") (pintype "input"))
    )
    (net (code "41") (name "/DVDD_IN") (class "Default")
      (node (ref "C24") (pin "1") (pinfunction "1_1") (pintype "passive"))
      (node (ref "D1") (pin "1") (pinfunction "C_1") (pintype "passive"))
      (node (ref "R16") (pin "2") (pinfunction "2_2") (pintype "passive"))
      (node (ref "TP18") (pin "1") (pintype "passive"))
      (node (ref "U9") (pin "3") (pinfunction "IN_3") (pintype "power_in"))
    )
    (net (code "42") (name "/LED_ADC") (class "Default")
      (node (ref "J1") (pin "16") (pinfunction "16_16") (pintype "passive"))
      (node (ref "U7") (pin "1") (pinfunction "Gate_1") (pintype "passive"))
    )
    (net (code "43") (name "/LED_ADC_DRAIN") (class "Default")
      (node (ref "DS1") (pin "2") (pinfunction "K_2") (pintype "passive"))
      (node (ref "U7") (pin "3") (pinfunction "Drain_3") (pintype "passive"))
    )
    (net (code "44") (name "/LED_ADC_MID") (class "Default")
      (node (ref "DS1") (pin "1") (pinfunction "A_1") (pintype "passive"))
      (node (ref "R12") (pin "1") (pinfunction "1_1") (pintype "passive"))
    )
    (net (code "45") (name "/LED_DAC") (class "Default")
      (node (ref "J3") (pin "16") (pinfunction "16_16") (pintype "passive"))
      (node (ref "U8") (pin "1") (pinfunction "Gate_1") (pintype "passive"))
    )
    (net (code "46") (name "/LED_DAC_DRAIN") (class "Default")
      (node (ref "DS2") (pin "2") (pinfunction "K_2") (pintype "passive"))
      (node (ref "U8") (pin "3") (pinfunction "Drain_3") (pintype "passive"))
    )
    (net (code "47") (name "/LED_DAC_MID") (class "Default")
      (node (ref "DS2") (pin "1") (pinfunction "A_1") (pintype "passive"))
      (node (ref "R13") (pin "1") (pinfunction "1_1") (pintype "passive"))
    )
    (net (code "48") (name "AVDD") (class "Default")
      (node (ref "C13") (pin "1") (pinfunction "1_1") (pintype "passive"))
      (node (ref "C15") (pin "1") (pinfunction "1_1") (pintype "passive"))
      (node (ref "C16") (pin "1") (pinfunction "1_1") (pintype "passive"))
      (node (ref "C22") (pin "1") (pinfunction "1_1") (pintype "passive"))
      (node (ref "C4") (pin "1") (pinfunction "1_1") (pintype "passive"))
      (node (ref "D2") (pin "2") (pinfunction "A_2") (pintype "passive"))
      (node (ref "P2") (pin "1") (pinfunction "1_1") (pintype "passive"))
      (node (ref "R12") (pin "2") (pinfunction "2_2") (pintype "passive"))
      (node (ref "R13") (pin "2") (pinfunction "2_2") (pintype "passive"))
      (node (ref "R18") (pin "2") (pinfunction "2_2") (pintype "passive"))
      (node (ref "TP17") (pin "1") (pintype "passive"))
      (node (ref "U1") (pin "13") (pinfunction "AVDD_13") (pintype "power_in"))
      (node (ref "U1") (pin "19") (pinfunction "AVDD_19") (pintype "power_in"))
      (node (ref "U4") (pin "4") (pinfunction "AVDD_4") (pintype "power_in"))
      (node (ref "U5") (pin "8") (pinfunction "V+_8") (pintype "power_in"))
      (node (ref "U6") (pin "2") (pinfunction "OUT_2") (pintype "power_in"))
      (node (ref "VR1") (pin "1") (pinfunction "CCW_1") (pintype "passive"))
      (node (ref "VR2") (pin "1") (pinfunction "CCW_1") (pintype "passive"))
    )
    (net (code "49") (name "DVDD") (class "Default")
      (node (ref "C11") (pin "1") (pinfunction "1_1") (pintype "passive"))
      (node (ref "C12") (pin "1") (pinfunction "1_1") (pintype "passive"))
      (node (ref "C14") (pin "1") (pinfunction "1_1") (pintype "passive"))
      (node (ref "C17") (pin "1") (pinfunction "1_1") (pintype "passive"))
      (node (ref "C18") (pin "1") (pinfunction "1_1") (pintype "passive"))
      (node (ref "C5") (pin "1") (pinfunction "1_1") (pintype "passive"))
      (node (ref "D1") (pin "2") (pinfunction "A_2") (pintype "passive"))
      (node (ref "R14") (pin "2") (pinfunction "2_2") (pintype "passive"))
      (node (ref "R6") (pin "2") (pinfunction "2_2") (pintype "passive"))
      (node (ref "R7") (pin "2") (pinfunction "2_2") (pintype "passive"))
      (node (ref "TP19") (pin "1") (pintype "passive"))
      (node (ref "U1") (pin "7") (pinfunction "DVDD_7") (pintype "power_in"))
      (node (ref "U2") (pin "5") (pinfunction "VCC_5") (pintype "power_in"))
      (node (ref "U3") (pin "5") (pinfunction "VCC_5") (pintype "power_in"))
      (node (ref "U4") (pin "12") (pinfunction "IOVDD_12") (pintype "power_in"))
      (node (ref "U9") (pin "2") (pinfunction "OUT_2") (pintype "power_in"))
    )
    (net (code "50") (name "GND") (class "Default")
      (node (ref "C1") (pin "2") (pinfunction "2_2") (pintype "passive"))
      (node (ref "C10") (pin "2") (pinfunction "2_2") (pintype "passive"))
      (node (ref "C11") (pin "2") (pinfunction "2_2") (pintype "passive"))
      (node (ref "C12") (pin "2") (pinfunction "2_2") (pintype "passive"))
      (node (ref "C13") (pin "2") (pinfunction "2_2") (pintype "passive"))
      (node (ref "C14") (pin "2") (pinfunction "2_2") (pintype "passive"))
      (node (ref "C15") (pin "2") (pinfunction "2_2") (pintype "passive"))
      (node (ref "C16") (pin "2") (pinfunction "2_2") (pintype "passive"))
      (node (ref "C17") (pin "2") (pinfunction "2_2") (pintype "passive"))
      (node (ref "C18") (pin "2") (pinfunction "2_2") (pintype "passive"))
      (node (ref "C19") (pin "2") (pinfunction "2_2") (pintype "passive"))
      (node (ref "C2") (pin "2") (pinfunction "2_2") (pintype "passive"))
      (node (ref "C20") (pin "2") (pinfunction "2_2") (pintype "passive"))
      (node (ref "C21") (pin "2") (pinfunction "2_2") (pintype "passive"))
      (node (ref "C22") (pin "2") (pinfunction "2_2") (pintype "passive"))
      (node (ref "C23") (pin "2") (pinfunction "2_2") (pintype "passive"))
      (node (ref "C24") (pin "2") (pinfunction "2_2") (pintype "passive"))
      (node (ref "C3") (pin "2") (pinfunction "2_2") (pintype "passive"))
      (node (ref "C4") (pin "2") (pinfunction "2_2") (pintype "passive"))
      (node (ref "C5") (pin "2") (pinfunction "2_2") (pintype "passive"))
      (node (ref "C6") (pin "2") (pinfunction "2_2") (pintype "passive"))
      (node (ref "C7") (pin "2") (pinfunction "2_2") (pintype "passive"))
      (node (ref "C8") (pin "2") (pinfunction "2_2") (pintype "passive"))
      (node (ref "C9") (pin "2") (pinfunction "2_2") (pintype "passive"))
      (node (ref "J1") (pin "1") (pinfunction "1_1") (pintype "passive"))
      (node (ref "J1") (pin "11") (pinfunction "11_11") (pintype "passive"))
      (node (ref "J1") (pin "13") (pinfunction "13_13") (pintype "passive"))
      (node (ref "J1") (pin "15") (pinfunction "15_15") (pintype "passive"))
      (node (ref "J1") (pin "3") (pinfunction "3_3") (pintype "passive"))
      (node (ref "J1") (pin "5") (pinfunction "5_5") (pintype "passive"))
      (node (ref "J1") (pin "7") (pinfunction "7_7") (pintype "passive"))
      (node (ref "J1") (pin "9") (pinfunction "9_9") (pintype "passive"))
      (node (ref "J2") (pin "1") (pinfunction "1_1") (pintype "passive"))
      (node (ref "J2") (pin "10") (pinfunction "10_10") (pintype "passive"))
      (node (ref "J2") (pin "11") (pinfunction "11_11") (pintype "passive"))
      (node (ref "J2") (pin "12") (pinfunction "12_12") (pintype "passive"))
      (node (ref "J2") (pin "13") (pinfunction "13_13") (pintype "passive"))
      (node (ref "J2") (pin "14") (pinfunction "14_14") (pintype "passive"))
      (node (ref "J2") (pin "15") (pinfunction "15_15") (pintype "passive"))
      (node (ref "J2") (pin "16") (pinfunction "16_16") (pintype "passive"))
      (node (ref "J2") (pin "3") (pinfunction "3_3") (pintype "passive"))
      (node (ref "J2") (pin "5") (pinfunction "5_5") (pintype "passive"))
      (node (ref "J2") (pin "6") (pinfunction "6_6") (pintype "passive"))
      (node (ref "J2") (pin "7") (pinfunction "7_7") (pintype "passive"))
      (node (ref "J2") (pin "8") (pinfunction "8_8") (pintype "passive"))
      (node (ref "J2") (pin "9") (pinfunction "9_9") (pintype "passive"))
      (node (ref "J3") (pin "1") (pinfunction "1_1") (pintype "passive"))
      (node (ref "J3") (pin "11") (pinfunction "11_11") (pintype "passive"))
      (node (ref "J3") (pin "13") (pinfunction "13_13") (pintype "passive"))
      (node (ref "J3") (pin "15") (pinfunction "15_15") (pintype "passive"))
      (node (ref "J3") (pin "3") (pinfunction "3_3") (pintype "passive"))
      (node (ref "J3") (pin "5") (pinfunction "5_5") (pintype "passive"))
      (node (ref "J3") (pin "7") (pinfunction "7_7") (pintype "passive"))
      (node (ref "J3") (pin "9") (pinfunction "9_9") (pintype "passive"))
      (node (ref "J5") (pin "1") (pinfunction "1_1") (pintype "passive"))
      (node (ref "JP1") (pin "10") (pinfunction "10_10") (pintype "passive"))
      (node (ref "JP1") (pin "12") (pinfunction "12_12") (pintype "passive"))
      (node (ref "JP1") (pin "14") (pinfunction "14_14") (pintype "passive"))
      (node (ref "JP1") (pin "16") (pinfunction "16_16") (pintype "passive"))
      (node (ref "JP1") (pin "2") (pinfunction "2_2") (pintype "passive"))
      (node (ref "JP1") (pin "4") (pinfunction "4_4") (pintype "passive"))
      (node (ref "JP1") (pin "6") (pinfunction "6_6") (pintype "passive"))
      (node (ref "JP1") (pin "8") (pinfunction "8_8") (pintype "passive"))
      (node (ref "MH1") (pin "PAD") (pinfunction "PAD_PAD") (pintype "passive"))
      (node (ref "MH2") (pin "PAD") (pinfunction "PAD_PAD") (pintype "passive"))
      (node (ref "MH3") (pin "PAD") (pinfunction "PAD_PAD") (pintype "passive"))
      (node (ref "MH4") (pin "PAD") (pinfunction "PAD_PAD") (pintype "passive"))
      (node (ref "P1") (pin "1") (pinfunction "1_1") (pintype "passive"))
      (node (ref "R15") (pin "1") (pinfunction "1_1") (pintype "passive"))
      (node (ref "R19") (pin "1") (pinfunction "1_1") (pintype "passive"))
      (node (ref "TP10") (pin "1") (pintype "passive"))
      (node (ref "TP12") (pin "1") (pintype "passive"))
      (node (ref "TP14") (pin "1") (pintype "passive"))
      (node (ref "TP16") (pin "1") (pintype "passive"))
      (node (ref "TP2") (pin "1") (pintype "passive"))
      (node (ref "TP20") (pin "1") (pintype "passive"))
      (node (ref "TP22") (pin "1") (pintype "passive"))
      (node (ref "TP4") (pin "1") (pintype "passive"))
      (node (ref "TP6") (pin "1") (pintype "passive"))
      (node (ref "TP8") (pin "1") (pintype "passive"))
      (node (ref "U1") (pin "14") (pinfunction "AGND_14") (pintype "power_in"))
      (node (ref "U1") (pin "16") (pinfunction "REFM_16") (pintype "input"))
      (node (ref "U1") (pin "18") (pinfunction "AGND_18") (pintype "power_in"))
      (node (ref "U1") (pin "6") (pinfunction "DGND_6") (pintype "power_in"))
      (node (ref "U2") (pin "3") (pinfunction "GND_3") (pintype "power_in"))
      (node (ref "U3") (pin "3") (pinfunction "GND_3") (pintype "power_in"))
      (node (ref "U4") (pin "5") (pinfunction "VREFL_5") (pintype "input"))
      (node (ref "U4") (pin "6") (pinfunction "GND_6") (pintype "power_in"))
      (node (ref "U5") (pin "4") (pinfunction "V-_4") (pintype "power_in"))
      (node (ref "U7") (pin "2") (pinfunction "Source_2") (pintype "passive"))
      (node (ref "U8") (pin "2") (pinfunction "Source_2") (pintype "passive"))
      (node (ref "VR1") (pin "3") (pinfunction "CW_3") (pintype "passive"))
      (node (ref "VR2") (pin "3") (pinfunction "CW_3") (pintype "passive"))
    )
    (net (code "51") (name "unconnected-(J1-Pad12)") (class "Default")
      (node (ref "J1") (pin "12") (pinfunction "12_12") (pintype "passive+no_connect"))
    )
    (net (code "52") (name "unconnected-(J1-Pad14)") (class "Default")
      (node (ref "J1") (pin "14") (pinfunction "14_14") (pintype "passive+no_connect"))
    )
    (net (code "53") (name "unconnected-(U2-NC-Pad1)") (class "Default")
      (node (ref "U2") (pin "1") (pinfunction "NC_1") (pintype "passive"))
    )
    (net (code "54") (name "unconnected-(U3-NC-Pad1)") (class "Default")
      (node (ref "U3") (pin "1") (pinfunction "NC_1") (pintype "passive"))
    )
    (net (code "55") (name "unconnected-(U6-TAB-Pad4)") (class "Default")
      (node (ref "U6") (pin "4") (pinfunction "TAB_4") (pintype "power_in"))
    )
    (net (code "56") (name "unconnected-(U9-TAB-Pad4)") (class "Default")
      (node (ref "U9") (pin "4") (pinfunction "TAB_4") (pintype "power_in"))
    )
  )
)
